# PhasedArray3.net
KiCad netlist of a schematic drawn in EAGLE
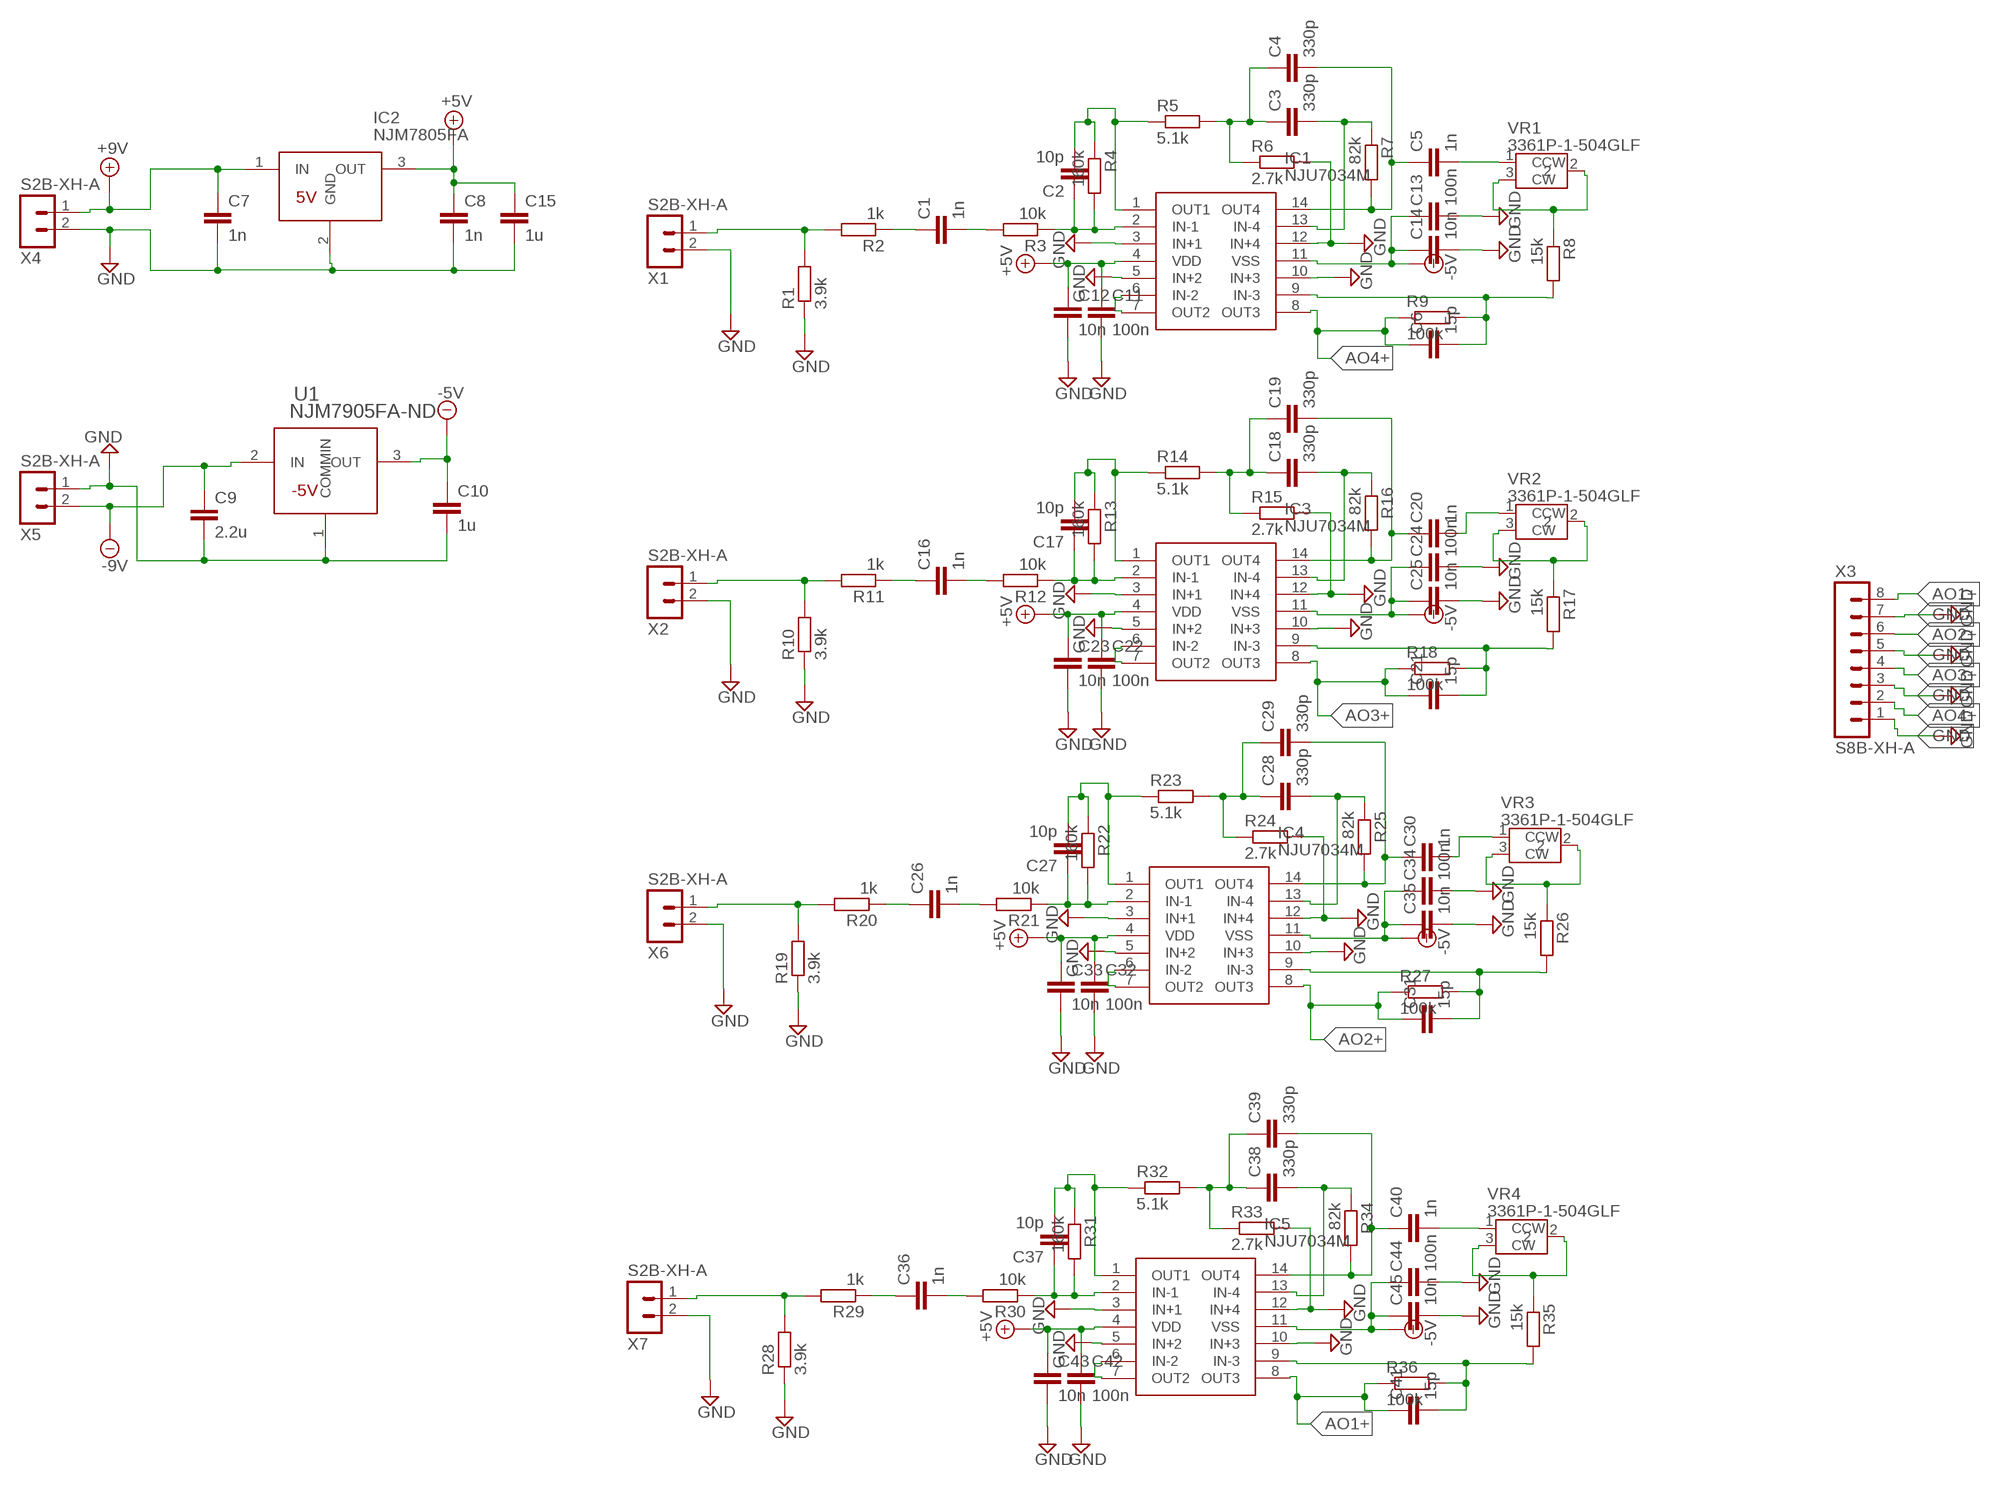
[diagram p0: schematic, sheet 1]

(export (version "E")
  (design (tool "Eeschema 10.0.6"))
  (components
    (comp (ref "C1")
      (value "1n")
      (footprint "eagle-import:C0603K")
      (libsource (lib "eagle-import") (part "C-EUC0603K"))
    )
    (comp (ref "C2")
      (value "10p")
      (footprint "eagle-import:C0603K")
      (libsource (lib "eagle-import") (part "C-EUC0603K"))
    )
    (comp (ref "C3")
      (value "330p")
      (footprint "eagle-import:C0603K")
      (libsource (lib "eagle-import") (part "C-EUC0603K"))
    )
    (comp (ref "C4")
      (value "330p")
      (footprint "eagle-import:C0603K")
      (libsource (lib "eagle-import") (part "C-EUC0603K"))
    )
    (comp (ref "C5")
      (value "1n")
      (footprint "eagle-import:C0603K")
      (libsource (lib "eagle-import") (part "C-EUC0603K"))
    )
    (comp (ref "C6")
      (value "15p")
      (footprint "eagle-import:C0603K")
      (libsource (lib "eagle-import") (part "C-EUC0603K"))
    )
    (comp (ref "C7")
      (value "1n")
      (footprint "eagle-import:C0603K")
      (libsource (lib "eagle-import") (part "C-EUC0603K"))
    )
    (comp (ref "C8")
      (value "1n")
      (footprint "eagle-import:C0603K")
      (libsource (lib "eagle-import") (part "C-EUC0603K"))
    )
    (comp (ref "C9")
      (value "2.2u")
      (footprint "eagle-import:C0805K")
      (libsource (lib "eagle-import") (part "C-EUC0805K"))
    )
    (comp (ref "C10")
      (value "1u")
      (footprint "eagle-import:C0805K")
      (libsource (lib "eagle-import") (part "C-EUC0805K"))
    )
    (comp (ref "C11")
      (value "100n")
      (footprint "eagle-import:C0603K")
      (libsource (lib "eagle-import") (part "C-EUC0603K"))
    )
    (comp (ref "C12")
      (value "10n")
      (footprint "eagle-import:C0603K")
      (libsource (lib "eagle-import") (part "C-EUC0603K"))
    )
    (comp (ref "C13")
      (value "100n")
      (footprint "eagle-import:C0603K")
      (libsource (lib "eagle-import") (part "C-EUC0603K"))
    )
    (comp (ref "C14")
      (value "10n")
      (footprint "eagle-import:C0603K")
      (libsource (lib "eagle-import") (part "C-EUC0603K"))
    )
    (comp (ref "C15")
      (value "1u")
      (footprint "eagle-import:C0805K")
      (libsource (lib "eagle-import") (part "C-EUC0805K"))
    )
    (comp (ref "C16")
      (value "1n")
      (footprint "eagle-import:C0603K")
      (libsource (lib "eagle-import") (part "C-EUC0603K"))
    )
    (comp (ref "C17")
      (value "10p")
      (footprint "eagle-import:C0603K")
      (libsource (lib "eagle-import") (part "C-EUC0603K"))
    )
    (comp (ref "C18")
      (value "330p")
      (footprint "eagle-import:C0603K")
      (libsource (lib "eagle-import") (part "C-EUC0603K"))
    )
    (comp (ref "C19")
      (value "330p")
      (footprint "eagle-import:C0603K")
      (libsource (lib "eagle-import") (part "C-EUC0603K"))
    )
    (comp (ref "C20")
      (value "1n")
      (footprint "eagle-import:C0603K")
      (libsource (lib "eagle-import") (part "C-EUC0603K"))
    )
    (comp (ref "C21")
      (value "15p")
      (footprint "eagle-import:C0603K")
      (libsource (lib "eagle-import") (part "C-EUC0603K"))
    )
    (comp (ref "C22")
      (value "100n")
      (footprint "eagle-import:C0603K")
      (libsource (lib "eagle-import") (part "C-EUC0603K"))
    )
    (comp (ref "C23")
      (value "10n")
      (footprint "eagle-import:C0603K")
      (libsource (lib "eagle-import") (part "C-EUC0603K"))
    )
    (comp (ref "C24")
      (value "100n")
      (footprint "eagle-import:C0603K")
      (libsource (lib "eagle-import") (part "C-EUC0603K"))
    )
    (comp (ref "C25")
      (value "10n")
      (footprint "eagle-import:C0603K")
      (libsource (lib "eagle-import") (part "C-EUC0603K"))
    )
    (comp (ref "C26")
      (value "1n")
      (footprint "eagle-import:C0603K")
      (libsource (lib "eagle-import") (part "C-EUC0603K"))
    )
    (comp (ref "C27")
      (value "10p")
      (footprint "eagle-import:C0603K")
      (libsource (lib "eagle-import") (part "C-EUC0603K"))
    )
    (comp (ref "C28")
      (value "330p")
      (footprint "eagle-import:C0603K")
      (libsource (lib "eagle-import") (part "C-EUC0603K"))
    )
    (comp (ref "C29")
      (value "330p")
      (footprint "eagle-import:C0603K")
      (libsource (lib "eagle-import") (part "C-EUC0603K"))
    )
    (comp (ref "C30")
      (value "1n")
      (footprint "eagle-import:C0603K")
      (libsource (lib "eagle-import") (part "C-EUC0603K"))
    )
    (comp (ref "C31")
      (value "15p")
      (footprint "eagle-import:C0603K")
      (libsource (lib "eagle-import") (part "C-EUC0603K"))
    )
    (comp (ref "C32")
      (value "100n")
      (footprint "eagle-import:C0603K")
      (libsource (lib "eagle-import") (part "C-EUC0603K"))
    )
    (comp (ref "C33")
      (value "10n")
      (footprint "eagle-import:C0603K")
      (libsource (lib "eagle-import") (part "C-EUC0603K"))
    )
    (comp (ref "C34")
      (value "100n")
      (footprint "eagle-import:C0603K")
      (libsource (lib "eagle-import") (part "C-EUC0603K"))
    )
    (comp (ref "C35")
      (value "10n")
      (footprint "eagle-import:C0603K")
      (libsource (lib "eagle-import") (part "C-EUC0603K"))
    )
    (comp (ref "C36")
      (value "1n")
      (footprint "eagle-import:C0603K")
      (libsource (lib "eagle-import") (part "C-EUC0603K"))
    )
    (comp (ref "C37")
      (value "10p")
      (footprint "eagle-import:C0603K")
      (libsource (lib "eagle-import") (part "C-EUC0603K"))
    )
    (comp (ref "C38")
      (value "330p")
      (footprint "eagle-import:C0603K")
      (libsource (lib "eagle-import") (part "C-EUC0603K"))
    )
    (comp (ref "C39")
      (value "330p")
      (footprint "eagle-import:C0603K")
      (libsource (lib "eagle-import") (part "C-EUC0603K"))
    )
    (comp (ref "C40")
      (value "1n")
      (footprint "eagle-import:C0603K")
      (libsource (lib "eagle-import") (part "C-EUC0603K"))
    )
    (comp (ref "C41")
      (value "15p")
      (footprint "eagle-import:C0603K")
      (libsource (lib "eagle-import") (part "C-EUC0603K"))
    )
    (comp (ref "C42")
      (value "100n")
      (footprint "eagle-import:C0603K")
      (libsource (lib "eagle-import") (part "C-EUC0603K"))
    )
    (comp (ref "C43")
      (value "10n")
      (footprint "eagle-import:C0603K")
      (libsource (lib "eagle-import") (part "C-EUC0603K"))
    )
    (comp (ref "C44")
      (value "100n")
      (footprint "eagle-import:C0603K")
      (libsource (lib "eagle-import") (part "C-EUC0603K"))
    )
    (comp (ref "C45")
      (value "10n")
      (footprint "eagle-import:C0603K")
      (libsource (lib "eagle-import") (part "C-EUC0603K"))
    )
    (comp (ref "IC1")
      (value "NJU7034M")
      (footprint "eagle-import:SOIC127P680X175-14N")
      (fields (field (name "MOUSER_PART_NUMBER") "513-NJU7034M"))
      (libsource (lib "eagle-import") (part "NJU7034M"))
    )
    (comp (ref "IC2")
      (value "NJM7805FA")
      (footprint "eagle-import:TO254P500X1000X2170-3P")
      (fields (field (name "MOUSER_PART_NUMBER") "513-NJM7805FA"))
      (libsource (lib "eagle-import") (part "NJM7805FA"))
    )
    (comp (ref "IC3")
      (value "NJU7034M")
      (footprint "eagle-import:SOIC127P680X175-14N")
      (fields (field (name "MOUSER_PART_NUMBER") "513-NJU7034M"))
      (libsource (lib "eagle-import") (part "NJU7034M"))
    )
    (comp (ref "IC4")
      (value "NJU7034M")
      (footprint "eagle-import:SOIC127P680X175-14N")
      (fields (field (name "MOUSER_PART_NUMBER") "513-NJU7034M"))
      (libsource (lib "eagle-import") (part "NJU7034M"))
    )
    (comp (ref "IC5")
      (value "NJU7034M")
      (footprint "eagle-import:SOIC127P680X175-14N")
      (fields (field (name "MOUSER_PART_NUMBER") "513-NJU7034M"))
      (libsource (lib "eagle-import") (part "NJU7034M"))
    )
    (comp (ref "R1")
      (value "3.9k")
      (footprint "eagle-import:R0603")
      (libsource (lib "eagle-import") (part "R-EU_R0603"))
    )
    (comp (ref "R2")
      (value "1k")
      (footprint "eagle-import:R0603")
      (libsource (lib "eagle-import") (part "R-EU_R0603"))
    )
    (comp (ref "R3")
      (value "10k")
      (footprint "eagle-import:R0603")
      (libsource (lib "eagle-import") (part "R-EU_R0603"))
    )
    (comp (ref "R4")
      (value "160k")
      (footprint "eagle-import:R0603")
      (libsource (lib "eagle-import") (part "R-EU_R0603"))
    )
    (comp (ref "R5")
      (value "5.1k")
      (footprint "eagle-import:R0603")
      (libsource (lib "eagle-import") (part "R-EU_R0603"))
    )
    (comp (ref "R6")
      (value "2.7k")
      (footprint "eagle-import:R0603")
      (libsource (lib "eagle-import") (part "R-EU_R0603"))
    )
    (comp (ref "R7")
      (value "82k")
      (footprint "eagle-import:R0603")
      (libsource (lib "eagle-import") (part "R-EU_R0603"))
    )
    (comp (ref "R8")
      (value "15k")
      (footprint "eagle-import:R0603")
      (libsource (lib "eagle-import") (part "R-EU_R0603"))
    )
    (comp (ref "R9")
      (value "100k")
      (footprint "eagle-import:R0603")
      (libsource (lib "eagle-import") (part "R-EU_R0603"))
    )
    (comp (ref "R10")
      (value "3.9k")
      (footprint "eagle-import:R0603")
      (libsource (lib "eagle-import") (part "R-EU_R0603"))
    )
    (comp (ref "R11")
      (value "1k")
      (footprint "eagle-import:R0603")
      (libsource (lib "eagle-import") (part "R-EU_R0603"))
    )
    (comp (ref "R12")
      (value "10k")
      (footprint "eagle-import:R0603")
      (libsource (lib "eagle-import") (part "R-EU_R0603"))
    )
    (comp (ref "R13")
      (value "160k")
      (footprint "eagle-import:R0603")
      (libsource (lib "eagle-import") (part "R-EU_R0603"))
    )
    (comp (ref "R14")
      (value "5.1k")
      (footprint "eagle-import:R0603")
      (libsource (lib "eagle-import") (part "R-EU_R0603"))
    )
    (comp (ref "R15")
      (value "2.7k")
      (footprint "eagle-import:R0603")
      (libsource (lib "eagle-import") (part "R-EU_R0603"))
    )
    (comp (ref "R16")
      (value "82k")
      (footprint "eagle-import:R0603")
      (libsource (lib "eagle-import") (part "R-EU_R0603"))
    )
    (comp (ref "R17")
      (value "15k")
      (footprint "eagle-import:R0603")
      (libsource (lib "eagle-import") (part "R-EU_R0603"))
    )
    (comp (ref "R18")
      (value "100k")
      (footprint "eagle-import:R0603")
      (libsource (lib "eagle-import") (part "R-EU_R0603"))
    )
    (comp (ref "R19")
      (value "3.9k")
      (footprint "eagle-import:R0603")
      (libsource (lib "eagle-import") (part "R-EU_R0603"))
    )
    (comp (ref "R20")
      (value "1k")
      (footprint "eagle-import:R0603")
      (libsource (lib "eagle-import") (part "R-EU_R0603"))
    )
    (comp (ref "R21")
      (value "10k")
      (footprint "eagle-import:R0603")
      (libsource (lib "eagle-import") (part "R-EU_R0603"))
    )
    (comp (ref "R22")
      (value "160k")
      (footprint "eagle-import:R0603")
      (libsource (lib "eagle-import") (part "R-EU_R0603"))
    )
    (comp (ref "R23")
      (value "5.1k")
      (footprint "eagle-import:R0603")
      (libsource (lib "eagle-import") (part "R-EU_R0603"))
    )
    (comp (ref "R24")
      (value "2.7k")
      (footprint "eagle-import:R0603")
      (libsource (lib "eagle-import") (part "R-EU_R0603"))
    )
    (comp (ref "R25")
      (value "82k")
      (footprint "eagle-import:R0603")
      (libsource (lib "eagle-import") (part "R-EU_R0603"))
    )
    (comp (ref "R26")
      (value "15k")
      (footprint "eagle-import:R0603")
      (libsource (lib "eagle-import") (part "R-EU_R0603"))
    )
    (comp (ref "R27")
      (value "100k")
      (footprint "eagle-import:R0603")
      (libsource (lib "eagle-import") (part "R-EU_R0603"))
    )
    (comp (ref "R28")
      (value "3.9k")
      (footprint "eagle-import:R0603")
      (libsource (lib "eagle-import") (part "R-EU_R0603"))
    )
    (comp (ref "R29")
      (value "1k")
      (footprint "eagle-import:R0603")
      (libsource (lib "eagle-import") (part "R-EU_R0603"))
    )
    (comp (ref "R30")
      (value "10k")
      (footprint "eagle-import:R0603")
      (libsource (lib "eagle-import") (part "R-EU_R0603"))
    )
    (comp (ref "R31")
      (value "160k")
      (footprint "eagle-import:R0603")
      (libsource (lib "eagle-import") (part "R-EU_R0603"))
    )
    (comp (ref "R32")
      (value "5.1k")
      (footprint "eagle-import:R0603")
      (libsource (lib "eagle-import") (part "R-EU_R0603"))
    )
    (comp (ref "R33")
      (value "2.7k")
      (footprint "eagle-import:R0603")
      (libsource (lib "eagle-import") (part "R-EU_R0603"))
    )
    (comp (ref "R34")
      (value "82k")
      (footprint "eagle-import:R0603")
      (libsource (lib "eagle-import") (part "R-EU_R0603"))
    )
    (comp (ref "R35")
      (value "15k")
      (footprint "eagle-import:R0603")
      (libsource (lib "eagle-import") (part "R-EU_R0603"))
    )
    (comp (ref "R36")
      (value "100k")
      (footprint "eagle-import:R0603")
      (libsource (lib "eagle-import") (part "R-EU_R0603"))
    )
    (comp (ref "U1")
      (value "NJM7905FA-ND")
      (footprint "eagle-import:NJR-TO-220F-3_NJR")
      (libsource (lib "eagle-import") (part "NJM7905FA-ND"))
    )
    (comp (ref "VR1")
      (value "3361P-1-504GLF")
      (footprint "eagle-import:3361P1253GLF")
      (fields (field (name "MOUSER_PART_NUMBER") "652-3361P-1-504GLF"))
      (libsource (lib "eagle-import") (part "3361P-1-504GLF"))
    )
    (comp (ref "VR2")
      (value "3361P-1-504GLF")
      (footprint "eagle-import:3361P1253GLF")
      (fields (field (name "MOUSER_PART_NUMBER") "652-3361P-1-504GLF"))
      (libsource (lib "eagle-import") (part "3361P-1-504GLF"))
    )
    (comp (ref "VR3")
      (value "3361P-1-504GLF")
      (footprint "eagle-import:3361P1253GLF")
      (fields (field (name "MOUSER_PART_NUMBER") "652-3361P-1-504GLF"))
      (libsource (lib "eagle-import") (part "3361P-1-504GLF"))
    )
    (comp (ref "VR4")
      (value "3361P-1-504GLF")
      (footprint "eagle-import:3361P1253GLF")
      (fields (field (name "MOUSER_PART_NUMBER") "652-3361P-1-504GLF"))
      (libsource (lib "eagle-import") (part "3361P-1-504GLF"))
    )
    (comp (ref "X1")
      (value "S2B-XH-A")
      (footprint "eagle-import:S2B-XH-A")
      (libsource (lib "eagle-import") (part "S2B-XH-A"))
    )
    (comp (ref "X2")
      (value "S2B-XH-A")
      (footprint "eagle-import:S2B-XH-A")
      (libsource (lib "eagle-import") (part "S2B-XH-A"))
    )
    (comp (ref "X3")
      (value "S8B-XH-A")
      (footprint "eagle-import:S8B-XH-A")
      (libsource (lib "eagle-import") (part "S8B-XH-A"))
    )
    (comp (ref "X4")
      (value "S2B-XH-A")
      (footprint "eagle-import:S2B-XH-A")
      (libsource (lib "eagle-import") (part "S2B-XH-A"))
    )
    (comp (ref "X5")
      (value "S2B-XH-A")
      (footprint "eagle-import:S2B-XH-A")
      (libsource (lib "eagle-import") (part "S2B-XH-A"))
    )
    (comp (ref "X6")
      (value "S2B-XH-A")
      (footprint "eagle-import:S2B-XH-A")
      (libsource (lib "eagle-import") (part "S2B-XH-A"))
    )
    (comp (ref "X7")
      (value "S2B-XH-A")
      (footprint "eagle-import:S2B-XH-A")
      (libsource (lib "eagle-import") (part "S2B-XH-A"))
    )
  )
  (nets
    (net (code "1") (name "+5V") (class "Default")
      (node (ref "C11") (pin "1") (pinfunction "1_1") (pintype "passive"))
      (node (ref "C12") (pin "1") (pinfunction "1_1") (pintype "passive"))
      (node (ref "C15") (pin "1") (pinfunction "1_1") (pintype "passive"))
      (node (ref "C22") (pin "1") (pinfunction "1_1") (pintype "passive"))
      (node (ref "C23") (pin "1") (pinfunction "1_1") (pintype "passive"))
      (node (ref "C32") (pin "1") (pinfunction "1_1") (pintype "passive"))
      (node (ref "C33") (pin "1") (pinfunction "1_1") (pintype "passive"))
      (node (ref "C42") (pin "1") (pinfunction "1_1") (pintype "passive"))
      (node (ref "C43") (pin "1") (pinfunction "1_1") (pintype "passive"))
      (node (ref "C8") (pin "1") (pinfunction "1_1") (pintype "passive"))
      (node (ref "IC1") (pin "4") (pinfunction "VDD_4") (pintype "bidirectional"))
      (node (ref "IC2") (pin "3") (pinfunction "OUT_3") (pintype "bidirectional"))
      (node (ref "IC3") (pin "4") (pinfunction "VDD_4") (pintype "bidirectional"))
      (node (ref "IC4") (pin "4") (pinfunction "VDD_4") (pintype "bidirectional"))
      (node (ref "IC5") (pin "4") (pinfunction "VDD_4") (pintype "bidirectional"))
    )
    (net (code "2") (name "+9V") (class "Default")
      (node (ref "C7") (pin "1") (pinfunction "1_1") (pintype "passive"))
      (node (ref "IC2") (pin "1") (pinfunction "IN_1") (pintype "bidirectional"))
      (node (ref "X4") (pin "1") (pinfunction "1_1") (pintype "passive"))
    )
    (net (code "3") (name "-5V") (class "Default")
      (node (ref "C10") (pin "1") (pinfunction "1_1") (pintype "passive"))
      (node (ref "C13") (pin "1") (pinfunction "1_1") (pintype "passive"))
      (node (ref "C14") (pin "1") (pinfunction "1_1") (pintype "passive"))
      (node (ref "C24") (pin "1") (pinfunction "1_1") (pintype "passive"))
      (node (ref "C25") (pin "1") (pinfunction "1_1") (pintype "passive"))
      (node (ref "C34") (pin "1") (pinfunction "1_1") (pintype "passive"))
      (node (ref "C35") (pin "1") (pinfunction "1_1") (pintype "passive"))
      (node (ref "C44") (pin "1") (pinfunction "1_1") (pintype "passive"))
      (node (ref "C45") (pin "1") (pinfunction "1_1") (pintype "passive"))
      (node (ref "IC1") (pin "11") (pinfunction "VSS_11") (pintype "bidirectional"))
      (node (ref "IC3") (pin "11") (pinfunction "VSS_11") (pintype "bidirectional"))
      (node (ref "IC4") (pin "11") (pinfunction "VSS_11") (pintype "bidirectional"))
      (node (ref "IC5") (pin "11") (pinfunction "VSS_11") (pintype "bidirectional"))
      (node (ref "U1") (pin "3") (pinfunction "OUT_3") (pintype "output"))
    )
    (net (code "4") (name "-9V") (class "Default")
      (node (ref "C9") (pin "1") (pinfunction "1_1") (pintype "passive"))
      (node (ref "U1") (pin "2") (pinfunction "IN_2") (pintype "input"))
      (node (ref "X5") (pin "2") (pinfunction "2_2") (pintype "passive"))
    )
    (net (code "5") (name "AO1+") (class "Default")
      (node (ref "C41") (pin "1") (pinfunction "1_1") (pintype "passive"))
      (node (ref "IC5") (pin "8") (pinfunction "OUT3_8") (pintype "bidirectional"))
      (node (ref "R36") (pin "1") (pinfunction "1_1") (pintype "passive"))
      (node (ref "X3") (pin "8") (pinfunction "8_8") (pintype "passive"))
    )
    (net (code "6") (name "AO2+") (class "Default")
      (node (ref "C31") (pin "1") (pinfunction "1_1") (pintype "passive"))
      (node (ref "IC4") (pin "8") (pinfunction "OUT3_8") (pintype "bidirectional"))
      (node (ref "R27") (pin "1") (pinfunction "1_1") (pintype "passive"))
      (node (ref "X3") (pin "6") (pinfunction "6_6") (pintype "passive"))
    )
    (net (code "7") (name "AO3+") (class "Default")
      (node (ref "C21") (pin "1") (pinfunction "1_1") (pintype "passive"))
      (node (ref "IC3") (pin "8") (pinfunction "OUT3_8") (pintype "bidirectional"))
      (node (ref "R18") (pin "1") (pinfunction "1_1") (pintype "passive"))
      (node (ref "X3") (pin "4") (pinfunction "4_4") (pintype "passive"))
    )
    (net (code "8") (name "AO4+") (class "Default")
      (node (ref "C6") (pin "1") (pinfunction "1_1") (pintype "passive"))
      (node (ref "IC1") (pin "8") (pinfunction "OUT3_8") (pintype "bidirectional"))
      (node (ref "R9") (pin "1") (pinfunction "1_1") (pintype "passive"))
      (node (ref "X3") (pin "2") (pinfunction "2_2") (pintype "passive"))
    )
    (net (code "9") (name "GND") (class "Default")
      (node (ref "C10") (pin "2") (pinfunction "2_2") (pintype "passive"))
      (node (ref "C11") (pin "2") (pinfunction "2_2") (pintype "passive"))
      (node (ref "C12") (pin "2") (pinfunction "2_2") (pintype "passive"))
      (node (ref "C13") (pin "2") (pinfunction "2_2") (pintype "passive"))
      (node (ref "C14") (pin "2") (pinfunction "2_2") (pintype "passive"))
      (node (ref "C15") (pin "2") (pinfunction "2_2") (pintype "passive"))
      (node (ref "C22") (pin "2") (pinfunction "2_2") (pintype "passive"))
      (node (ref "C23") (pin "2") (pinfunction "2_2") (pintype "passive"))
      (node (ref "C24") (pin "2") (pinfunction "2_2") (pintype "passive"))
      (node (ref "C25") (pin "2") (pinfunction "2_2") (pintype "passive"))
      (node (ref "C32") (pin "2") (pinfunction "2_2") (pintype "passive"))
      (node (ref "C33") (pin "2") (pinfunction "2_2") (pintype "passive"))
      (node (ref "C34") (pin "2") (pinfunction "2_2") (pintype "passive"))
      (node (ref "C35") (pin "2") (pinfunction "2_2") (pintype "passive"))
      (node (ref "C42") (pin "2") (pinfunction "2_2") (pintype "passive"))
      (node (ref "C43") (pin "2") (pinfunction "2_2") (pintype "passive"))
      (node (ref "C44") (pin "2") (pinfunction "2_2") (pintype "passive"))
      (node (ref "C45") (pin "2") (pinfunction "2_2") (pintype "passive"))
      (node (ref "C7") (pin "2") (pinfunction "2_2") (pintype "passive"))
      (node (ref "C8") (pin "2") (pinfunction "2_2") (pintype "passive"))
      (node (ref "C9") (pin "2") (pinfunction "2_2") (pintype "passive"))
      (node (ref "IC1") (pin "10") (pinfunction "IN+3_10") (pintype "bidirectional"))
      (node (ref "IC1") (pin "12") (pinfunction "IN+4_12") (pintype "bidirectional"))
      (node (ref "IC1") (pin "3") (pinfunction "IN+1_3") (pintype "bidirectional"))
      (node (ref "IC1") (pin "5") (pinfunction "IN+2_5") (pintype "bidirectional"))
      (node (ref "IC2") (pin "2") (pinfunction "GND_2") (pintype "bidirectional"))
      (node (ref "IC3") (pin "10") (pinfunction "IN+3_10") (pintype "bidirectional"))
      (node (ref "IC3") (pin "12") (pinfunction "IN+4_12") (pintype "bidirectional"))
      (node (ref "IC3") (pin "3") (pinfunction "IN+1_3") (pintype "bidirectional"))
      (node (ref "IC3") (pin "5") (pinfunction "IN+2_5") (pintype "bidirectional"))
      (node (ref "IC4") (pin "10") (pinfunction "IN+3_10") (pintype "bidirectional"))
      (node (ref "IC4") (pin "12") (pinfunction "IN+4_12") (pintype "bidirectional"))
      (node (ref "IC4") (pin "3") (pinfunction "IN+1_3") (pintype "bidirectional"))
      (node (ref "IC4") (pin "5") (pinfunction "IN+2_5") (pintype "bidirectional"))
      (node (ref "IC5") (pin "10") (pinfunction "IN+3_10") (pintype "bidirectional"))
      (node (ref "IC5") (pin "12") (pinfunction "IN+4_12") (pintype "bidirectional"))
      (node (ref "IC5") (pin "3") (pinfunction "IN+1_3") (pintype "bidirectional"))
      (node (ref "IC5") (pin "5") (pinfunction "IN+2_5") (pintype "bidirectional"))
      (node (ref "R1") (pin "1") (pinfunction "1_1") (pintype "passive"))
      (node (ref "R10") (pin "1") (pinfunction "1_1") (pintype "passive"))
      (node (ref "R15") (pin "2") (pinfunction "2_2") (pintype "passive"))
      (node (ref "R19") (pin "1") (pinfunction "1_1") (pintype "passive"))
      (node (ref "R24") (pin "2") (pinfunction "2_2") (pintype "passive"))
      (node (ref "R28") (pin "1") (pinfunction "1_1") (pintype "passive"))
      (node (ref "R33") (pin "2") (pinfunction "2_2") (pintype "passive"))
      (node (ref "R6") (pin "2") (pinfunction "2_2") (pintype "passive"))
      (node (ref "U1") (pin "1") (pinfunction "COMMIN_1") (pintype "passive"))
      (node (ref "X1") (pin "2") (pinfunction "2_2") (pintype "passive"))
      (node (ref "X2") (pin "2") (pinfunction "2_2") (pintype "passive"))
      (node (ref "X3") (pin "1") (pinfunction "1_1") (pintype "passive"))
      (node (ref "X3") (pin "3") (pinfunction "3_3") (pintype "passive"))
      (node (ref "X3") (pin "5") (pinfunction "5_5") (pintype "passive"))
      (node (ref "X3") (pin "7") (pinfunction "7_7") (pintype "passive"))
      (node (ref "X4") (pin "2") (pinfunction "2_2") (pintype "passive"))
      (node (ref "X5") (pin "1") (pinfunction "1_1") (pintype "passive"))
      (node (ref "X6") (pin "2") (pinfunction "2_2") (pintype "passive"))
      (node (ref "X7") (pin "2") (pinfunction "2_2") (pintype "passive"))
    )
    (net (code "10") (name "Net-(C1-Pad1)") (class "Default")
      (node (ref "C1") (pin "1") (pinfunction "1_1") (pintype "passive"))
      (node (ref "R2") (pin "1") (pinfunction "1_1") (pintype "passive"))
    )
    (net (code "11") (name "Net-(C1-Pad2)") (class "Default")
      (node (ref "C1") (pin "2") (pinfunction "2_2") (pintype "passive"))
      (node (ref "R3") (pin "2") (pinfunction "2_2") (pintype "passive"))
    )
    (net (code "12") (name "Net-(C3-Pad1)") (class "Default")
      (node (ref "C3") (pin "1") (pinfunction "1_1") (pintype "passive"))
      (node (ref "C4") (pin "1") (pinfunction "1_1") (pintype "passive"))
      (node (ref "R5") (pin "2") (pinfunction "2_2") (pintype "passive"))
      (node (ref "R6") (pin "1") (pinfunction "1_1") (pintype "passive"))
    )
    (net (code "13") (name "Net-(C16-Pad1)") (class "Default")
      (node (ref "C16") (pin "1") (pinfunction "1_1") (pintype "passive"))
      (node (ref "R11") (pin "1") (pinfunction "1_1") (pintype "passive"))
    )
    (net (code "14") (name "Net-(C16-Pad2)") (class "Default")
      (node (ref "C16") (pin "2") (pinfunction "2_2") (pintype "passive"))
      (node (ref "R12") (pin "2") (pinfunction "2_2") (pintype "passive"))
    )
    (net (code "15") (name "Net-(C18-Pad1)") (class "Default")
      (node (ref "C18") (pin "1") (pinfunction "1_1") (pintype "passive"))
      (node (ref "C19") (pin "1") (pinfunction "1_1") (pintype "passive"))
      (node (ref "R14") (pin "2") (pinfunction "2_2") (pintype "passive"))
      (node (ref "R15") (pin "1") (pinfunction "1_1") (pintype "passive"))
    )
    (net (code "16") (name "Net-(C26-Pad1)") (class "Default")
      (node (ref "C26") (pin "1") (pinfunction "1_1") (pintype "passive"))
      (node (ref "R20") (pin "1") (pinfunction "1_1") (pintype "passive"))
    )
    (net (code "17") (name "Net-(C26-Pad2)") (class "Default")
      (node (ref "C26") (pin "2") (pinfunction "2_2") (pintype "passive"))
      (node (ref "R21") (pin "2") (pinfunction "2_2") (pintype "passive"))
    )
    (net (code "18") (name "Net-(C28-Pad1)") (class "Default")
      (node (ref "C28") (pin "1") (pinfunction "1_1") (pintype "passive"))
      (node (ref "C29") (pin "1") (pinfunction "1_1") (pintype "passive"))
      (node (ref "R23") (pin "2") (pinfunction "2_2") (pintype "passive"))
      (node (ref "R24") (pin "1") (pinfunction "1_1") (pintype "passive"))
    )
    (net (code "19") (name "Net-(C36-Pad1)") (class "Default")
      (node (ref "C36") (pin "1") (pinfunction "1_1") (pintype "passive"))
      (node (ref "R29") (pin "1") (pinfunction "1_1") (pintype "passive"))
    )
    (net (code "20") (name "Net-(C36-Pad2)") (class "Default")
      (node (ref "C36") (pin "2") (pinfunction "2_2") (pintype "passive"))
      (node (ref "R30") (pin "2") (pinfunction "2_2") (pintype "passive"))
    )
    (net (code "21") (name "Net-(C38-Pad1)") (class "Default")
      (node (ref "C38") (pin "1") (pinfunction "1_1") (pintype "passive"))
      (node (ref "C39") (pin "1") (pinfunction "1_1") (pintype "passive"))
      (node (ref "R32") (pin "2") (pinfunction "2_2") (pintype "passive"))
      (node (ref "R33") (pin "1") (pinfunction "1_1") (pintype "passive"))
    )
    (net (code "22") (name "Net-(IC1-IN-1)") (class "Default")
      (node (ref "C2") (pin "1") (pinfunction "1_1") (pintype "passive"))
      (node (ref "IC1") (pin "2") (pinfunction "IN-1_2") (pintype "bidirectional"))
      (node (ref "R3") (pin "1") (pinfunction "1_1") (pintype "passive"))
      (node (ref "R4") (pin "2") (pinfunction "2_2") (pintype "passive"))
    )
    (net (code "23") (name "Net-(IC1-IN-2)") (class "Default")
      (node (ref "IC1") (pin "6") (pinfunction "IN-2_6") (pintype "bidirectional"))
      (node (ref "IC1") (pin "7") (pinfunction "OUT2_7") (pintype "bidirectional"))
    )
    (net (code "24") (name "Net-(IC1-IN-3)") (class "Default")
      (node (ref "C6") (pin "2") (pinfunction "2_2") (pintype "passive"))
      (node (ref "IC1") (pin "9") (pinfunction "IN-3_9") (pintype "bidirectional"))
      (node (ref "R8") (pin "2") (pinfunction "2_2") (pintype "passive"))
      (node (ref "R9") (pin "2") (pinfunction "2_2") (pintype "passive"))
    )
    (net (code "25") (name "Net-(IC1-IN-4)") (class "Default")
      (node (ref "C3") (pin "2") (pinfunction "2_2") (pintype "passive"))
      (node (ref "IC1") (pin "13") (pinfunction "IN-4_13") (pintype "bidirectional"))
      (node (ref "R7") (pin "1") (pinfunction "1_1") (pintype "passive"))
    )
    (net (code "26") (name "Net-(IC1-OUT1)") (class "Default")
      (node (ref "C2") (pin "2") (pinfunction "2_2") (pintype "passive"))
      (node (ref "IC1") (pin "1") (pinfunction "OUT1_1") (pintype "bidirectional"))
      (node (ref "R4") (pin "1") (pinfunction "1_1") (pintype "passive"))
      (node (ref "R5") (pin "1") (pinfunction "1_1") (pintype "passive"))
    )
    (net (code "27") (name "Net-(IC1-OUT4)") (class "Default")
      (node (ref "C4") (pin "2") (pinfunction "2_2") (pintype "passive"))
      (node (ref "C5") (pin "1") (pinfunction "1_1") (pintype "passive"))
      (node (ref "IC1") (pin "14") (pinfunction "OUT4_14") (pintype "bidirectional"))
      (node (ref "R7") (pin "2") (pinfunction "2_2") (pintype "passive"))
    )
    (net (code "28") (name "Net-(IC3-IN-1)") (class "Default")
      (node (ref "C17") (pin "1") (pinfunction "1_1") (pintype "passive"))
      (node (ref "IC3") (pin "2") (pinfunction "IN-1_2") (pintype "bidirectional"))
      (node (ref "R12") (pin "1") (pinfunction "1_1") (pintype "passive"))
      (node (ref "R13") (pin "2") (pinfunction "2_2") (pintype "passive"))
    )
    (net (code "29") (name "Net-(IC3-IN-2)") (class "Default")
      (node (ref "IC3") (pin "6") (pinfunction "IN-2_6") (pintype "bidirectional"))
      (node (ref "IC3") (pin "7") (pinfunction "OUT2_7") (pintype "bidirectional"))
    )
    (net (code "30") (name "Net-(IC3-IN-3)") (class "Default")
      (node (ref "C21") (pin "2") (pinfunction "2_2") (pintype "passive"))
      (node (ref "IC3") (pin "9") (pinfunction "IN-3_9") (pintype "bidirectional"))
      (node (ref "R17") (pin "2") (pinfunction "2_2") (pintype "passive"))
      (node (ref "R18") (pin "2") (pinfunction "2_2") (pintype "passive"))
    )
    (net (code "31") (name "Net-(IC3-IN-4)") (class "Default")
      (node (ref "C18") (pin "2") (pinfunction "2_2") (pintype "passive"))
      (node (ref "IC3") (pin "13") (pinfunction "IN-4_13") (pintype "bidirectional"))
      (node (ref "R16") (pin "1") (pinfunction "1_1") (pintype "passive"))
    )
    (net (code "32") (name "Net-(IC3-OUT1)") (class "Default")
      (node (ref "C17") (pin "2") (pinfunction "2_2") (pintype "passive"))
      (node (ref "IC3") (pin "1") (pinfunction "OUT1_1") (pintype "bidirectional"))
      (node (ref "R13") (pin "1") (pinfunction "1_1") (pintype "passive"))
      (node (ref "R14") (pin "1") (pinfunction "1_1") (pintype "passive"))
    )
    (net (code "33") (name "Net-(IC3-OUT4)") (class "Default")
      (node (ref "C19") (pin "2") (pinfunction "2_2") (pintype "passive"))
      (node (ref "C20") (pin "1") (pinfunction "1_1") (pintype "passive"))
      (node (ref "IC3") (pin "14") (pinfunction "OUT4_14") (pintype "bidirectional"))
      (node (ref "R16") (pin "2") (pinfunction "2_2") (pintype "passive"))
    )
    (net (code "34") (name "Net-(IC4-IN-1)") (class "Default")
      (node (ref "C27") (pin "1") (pinfunction "1_1") (pintype "passive"))
      (node (ref "IC4") (pin "2") (pinfunction "IN-1_2") (pintype "bidirectional"))
      (node (ref "R21") (pin "1") (pinfunction "1_1") (pintype "passive"))
      (node (ref "R22") (pin "2") (pinfunction "2_2") (pintype "passive"))
    )
    (net (code "35") (name "Net-(IC4-IN-2)") (class "Default")
      (node (ref "IC4") (pin "6") (pinfunction "IN-2_6") (pintype "bidirectional"))
      (node (ref "IC4") (pin "7") (pinfunction "OUT2_7") (pintype "bidirectional"))
    )
    (net (code "36") (name "Net-(IC4-IN-3)") (class "Default")
      (node (ref "C31") (pin "2") (pinfunction "2_2") (pintype "passive"))
      (node (ref "IC4") (pin "9") (pinfunction "IN-3_9") (pintype "bidirectional"))
      (node (ref "R26") (pin "2") (pinfunction "2_2") (pintype "passive"))
      (node (ref "R27") (pin "2") (pinfunction "2_2") (pintype "passive"))
    )
    (net (code "37") (name "Net-(IC4-IN-4)") (class "Default")
      (node (ref "C28") (pin "2") (pinfunction "2_2") (pintype "passive"))
      (node (ref "IC4") (pin "13") (pinfunction "IN-4_13") (pintype "bidirectional"))
      (node (ref "R25") (pin "1") (pinfunction "1_1") (pintype "passive"))
    )
    (net (code "38") (name "Net-(IC4-OUT1)") (class "Default")
      (node (ref "C27") (pin "2") (pinfunction "2_2") (pintype "passive"))
      (node (ref "IC4") (pin "1") (pinfunction "OUT1_1") (pintype "bidirectional"))
      (node (ref "R22") (pin "1") (pinfunction "1_1") (pintype "passive"))
      (node (ref "R23") (pin "1") (pinfunction "1_1") (pintype "passive"))
    )
    (net (code "39") (name "Net-(IC4-OUT4)") (class "Default")
      (node (ref "C29") (pin "2") (pinfunction "2_2") (pintype "passive"))
      (node (ref "C30") (pin "1") (pinfunction "1_1") (pintype "passive"))
      (node (ref "IC4") (pin "14") (pinfunction "OUT4_14") (pintype "bidirectional"))
      (node (ref "R25") (pin "2") (pinfunction "2_2") (pintype "passive"))
    )
    (net (code "40") (name "Net-(IC5-IN-1)") (class "Default")
      (node (ref "C37") (pin "1") (pinfunction "1_1") (pintype "passive"))
      (node (ref "IC5") (pin "2") (pinfunction "IN-1_2") (pintype "bidirectional"))
      (node (ref "R30") (pin "1") (pinfunction "1_1") (pintype "passive"))
      (node (ref "R31") (pin "2") (pinfunction "2_2") (pintype "passive"))
    )
    (net (code "41") (name "Net-(IC5-IN-2)") (class "Default")
      (node (ref "IC5") (pin "6") (pinfunction "IN-2_6") (pintype "bidirectional"))
      (node (ref "IC5") (pin "7") (pinfunction "OUT2_7") (pintype "bidirectional"))
    )
    (net (code "42") (name "Net-(IC5-IN-3)") (class "Default")
      (node (ref "C41") (pin "2") (pinfunction "2_2") (pintype "passive"))
      (node (ref "IC5") (pin "9") (pinfunction "IN-3_9") (pintype "bidirectional"))
      (node (ref "R35") (pin "2") (pinfunction "2_2") (pintype "passive"))
      (node (ref "R36") (pin "2") (pinfunction "2_2") (pintype "passive"))
    )
    (net (code "43") (name "Net-(IC5-IN-4)") (class "Default")
      (node (ref "C38") (pin "2") (pinfunction "2_2") (pintype "passive"))
      (node (ref "IC5") (pin "13") (pinfunction "IN-4_13") (pintype "bidirectional"))
      (node (ref "R34") (pin "1") (pinfunction "1_1") (pintype "passive"))
    )
    (net (code "44") (name "Net-(IC5-OUT1)") (class "Default")
      (node (ref "C37") (pin "2") (pinfunction "2_2") (pintype "passive"))
      (node (ref "IC5") (pin "1") (pinfunction "OUT1_1") (pintype "bidirectional"))
      (node (ref "R31") (pin "1") (pinfunction "1_1") (pintype "passive"))
      (node (ref "R32") (pin "1") (pinfunction "1_1") (pintype "passive"))
    )
    (net (code "45") (name "Net-(IC5-OUT4)") (class "Default")
      (node (ref "C39") (pin "2") (pinfunction "2_2") (pintype "passive"))
      (node (ref "C40") (pin "1") (pinfunction "1_1") (pintype "passive"))
      (node (ref "IC5") (pin "14") (pinfunction "OUT4_14") (pintype "bidirectional"))
      (node (ref "R34") (pin "2") (pinfunction "2_2") (pintype "passive"))
    )
    (net (code "46") (name "Net-(R1-Pad2)") (class "Default")
      (node (ref "R1") (pin "2") (pinfunction "2_2") (pintype "passive"))
      (node (ref "R2") (pin "2") (pinfunction "2_2") (pintype "passive"))
      (node (ref "X1") (pin "1") (pinfunction "1_1") (pintype "passive"))
    )
    (net (code "47") (name "Net-(R10-Pad2)") (class "Default")
      (node (ref "R10") (pin "2") (pinfunction "2_2") (pintype "passive"))
      (node (ref "R11") (pin "2") (pinfunction "2_2") (pintype "passive"))
      (node (ref "X2") (pin "1") (pinfunction "1_1") (pintype "passive"))
    )
    (net (code "48") (name "Net-(R19-Pad2)") (class "Default")
      (node (ref "R19") (pin "2") (pinfunction "2_2") (pintype "passive"))
      (node (ref "R20") (pin "2") (pinfunction "2_2") (pintype "passive"))
      (node (ref "X6") (pin "1") (pinfunction "1_1") (pintype "passive"))
    )
    (net (code "49") (name "Net-(R28-Pad2)") (class "Default")
      (node (ref "R28") (pin "2") (pinfunction "2_2") (pintype "passive"))
      (node (ref "R29") (pin "2") (pinfunction "2_2") (pintype "passive"))
      (node (ref "X7") (pin "1") (pinfunction "1_1") (pintype "passive"))
    )
    (net (code "50") (name "Net-(VR1-CCW)") (class "Default")
      (node (ref "C5") (pin "2") (pinfunction "2_2") (pintype "passive"))
      (node (ref "VR1") (pin "1") (pinfunction "CCW_1") (pintype "bidirectional"))
    )
    (net (code "51") (name "Net-(VR1-CW)") (class "Default")
      (node (ref "R8") (pin "1") (pinfunction "1_1") (pintype "passive"))
      (node (ref "VR1") (pin "2") (pinfunction "2_2") (pintype "bidirectional"))
      (node (ref "VR1") (pin "3") (pinfunction "CW_3") (pintype "bidirectional"))
    )
    (net (code "52") (name "Net-(VR2-CCW)") (class "Default")
      (node (ref "C20") (pin "2") (pinfunction "2_2") (pintype "passive"))
      (node (ref "VR2") (pin "1") (pinfunction "CCW_1") (pintype "bidirectional"))
    )
    (net (code "53") (name "Net-(VR2-CW)") (class "Default")
      (node (ref "R17") (pin "1") (pinfunction "1_1") (pintype "passive"))
      (node (ref "VR2") (pin "2") (pinfunction "2_2") (pintype "bidirectional"))
      (node (ref "VR2") (pin "3") (pinfunction "CW_3") (pintype "bidirectional"))
    )
    (net (code "54") (name "Net-(VR3-CCW)") (class "Default")
      (node (ref "C30") (pin "2") (pinfunction "2_2") (pintype "passive"))
      (node (ref "VR3") (pin "1") (pinfunction "CCW_1") (pintype "bidirectional"))
    )
    (net (code "55") (name "Net-(VR3-CW)") (class "Default")
      (node (ref "R26") (pin "1") (pinfunction "1_1") (pintype "passive"))
      (node (ref "VR3") (pin "2") (pinfunction "2_2") (pintype "bidirectional"))
      (node (ref "VR3") (pin "3") (pinfunction "CW_3") (pintype "bidirectional"))
    )
    (net (code "56") (name "Net-(VR4-CCW)") (class "Default")
      (node (ref "C40") (pin "2") (pinfunction "2_2") (pintype "passive"))
      (node (ref "VR4") (pin "1") (pinfunction "CCW_1") (pintype "bidirectional"))
    )
    (net (code "57") (name "Net-(VR4-CW)") (class "Default")
      (node (ref "R35") (pin "1") (pinfunction "1_1") (pintype "passive"))
      (node (ref "VR4") (pin "2") (pinfunction "2_2") (pintype "bidirectional"))
      (node (ref "VR4") (pin "3") (pinfunction "CW_3") (pintype "bidirectional"))
    )
  )
)
